# Sheet1.net
KiCad netlist of a schematic drawn in Altium Designer
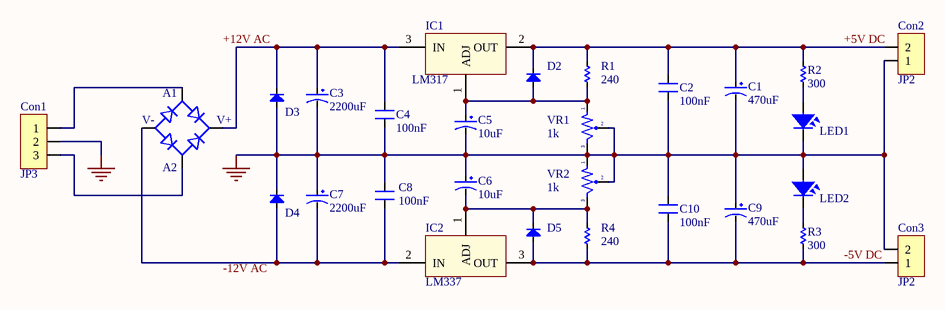
[diagram p0: Sheet1.SchDoc]

(export (version "E")
  (design (tool "Eeschema 10.0.6"))
  (components
    (comp (ref "C1")
      (value "470uF")
      (footprint "CA-ALU-6.3")
      (description "Polarized")
      (libsource (lib "KhiemLab") (part "Capacitor P"))
    )
    (comp (ref "C2")
      (value "100nF")
      (footprint "CN1.5")
      (description "Non-polarized")
      (libsource (lib "KhiemLab") (part "Capacitor NP"))
    )
    (comp (ref "C3")
      (value "2200uF")
      (footprint "CA-ALU-10")
      (description "Polarized")
      (libsource (lib "KhiemLab") (part "Capacitor P"))
    )
    (comp (ref "C4")
      (value "100nF")
      (footprint "CN1.5")
      (description "Non-polarized")
      (libsource (lib "KhiemLab") (part "Capacitor NP"))
    )
    (comp (ref "C5")
      (value "10uF")
      (footprint "CA-ALU-5")
      (description "Polarized")
      (libsource (lib "KhiemLab") (part "Capacitor P"))
    )
    (comp (ref "C6")
      (value "10uF")
      (footprint "CA-ALU-5")
      (description "Polarized")
      (libsource (lib "KhiemLab") (part "Capacitor P"))
    )
    (comp (ref "C7")
      (value "2200uF")
      (footprint "CA-ALU-10")
      (description "Polarized")
      (libsource (lib "KhiemLab") (part "Capacitor P"))
    )
    (comp (ref "C8")
      (value "100nF")
      (footprint "CN1.5")
      (description "Non-polarized")
      (libsource (lib "KhiemLab") (part "Capacitor NP"))
    )
    (comp (ref "C9")
      (value "470uF")
      (footprint "CA-ALU-6.3")
      (description "Polarized")
      (libsource (lib "KhiemLab") (part "Capacitor P"))
    )
    (comp (ref "C10")
      (value "100nF")
      (footprint "CN1.5")
      (description "Non-polarized")
      (libsource (lib "KhiemLab") (part "Capacitor NP"))
    )
    (comp (ref "Con1")
      (value "JP3")
      (footprint "KF3-3.5")
      (description "male/female")
      (fields
        (field (name "MANUFACTURER") "Würth Elektronik eiSos GmbH")
        (field (name "PARTNO") "613003143121")
        (field (name "CREATED BY") "Karrer Zheng")
      )
      (libsource (lib "KhiemLab") (part "Header 3"))
    )
    (comp (ref "Con2")
      (value "JP2")
      (footprint "KF2-3.5")
      (description "male/female")
      (fields
        (field (name "MANUFACTURER") "Würth Elektronik eiSos GmbH")
        (field (name "PARTNO") "613002143121")
        (field (name "CREATED BY") "Karrer Zheng")
      )
      (libsource (lib "KhiemLab") (part "Header 2"))
    )
    (comp (ref "Con3")
      (value "JP2")
      (footprint "KF2-3.5")
      (description "male/female")
      (fields
        (field (name "MANUFACTURER") "Würth Elektronik eiSos GmbH")
        (field (name "PARTNO") "613002143121")
        (field (name "CREATED BY") "Karrer Zheng")
      )
      (libsource (lib "KhiemLab") (part "Header 2"))
    )
    (comp (ref "D2")
      (value "Diode")
      (footprint "DIO-1A-SMALL")
      (description "Default Diode")
      (fields (field (name "PUBLISHER") "Altium Limited"))
      (libsource (lib "KhiemLab") (part "Diode"))
    )
    (comp (ref "D3")
      (value "Diode")
      (footprint "DIO-1A-SMALL")
      (description "Default Diode")
      (fields (field (name "PUBLISHER") "Altium Limited"))
      (libsource (lib "KhiemLab") (part "Diode"))
    )
    (comp (ref "D4")
      (value "Diode")
      (footprint "DIO-1A-SMALL")
      (description "Default Diode")
      (fields (field (name "PUBLISHER") "Altium Limited"))
      (libsource (lib "KhiemLab") (part "Diode"))
    )
    (comp (ref "D5")
      (value "Diode")
      (footprint "DIO-1A-SMALL")
      (description "Default Diode")
      (fields (field (name "PUBLISHER") "Altium Limited"))
      (libsource (lib "KhiemLab") (part "Diode"))
    )
    (comp (ref "DB1")
      (value "Diode Brideg")
      (footprint "DIO-Bri 5A")
      (description "Convert AC to DC voltage, 4 pin")
      (libsource (lib "KhiemLab") (part "Diode Brigde"))
    )
    (comp (ref "IC1")
      (value "LM317")
      (footprint "TO220H2")
      (description "Adj Voltage +1.2 -> +37V")
      (libsource (lib "KhiemLab") (part "LM317"))
    )
    (comp (ref "IC2")
      (value "LM337")
      (footprint "TO220H2")
      (description "On ap (-)     -1.2 -> - 37V")
      (libsource (lib "KhiemLab") (part "LM337"))
    )
    (comp (ref "LED1")
      (value "LED")
      (footprint "LED-5-RED")
      (description "LED Single colour")
      (libsource (lib "KhiemLab") (part "LED"))
    )
    (comp (ref "LED2")
      (value "LED")
      (footprint "LED-5-RED")
      (description "LED Single colour")
      (libsource (lib "KhiemLab") (part "LED"))
    )
    (comp (ref "R1")
      (value "240")
      (footprint "RES-1/4W-SMALL")
      (fields
        (field (name "MANUFACTURER") "Generic Components")
        (field (name "PUBLISHER") "Altium Hobart Technology Centre")
      )
      (libsource (lib "KhiemLab") (part "Resistor"))
    )
    (comp (ref "R2")
      (value "300")
      (footprint "RES-1/4W-SMALL")
      (fields
        (field (name "MANUFACTURER") "Generic Components")
        (field (name "PUBLISHER") "Altium Hobart Technology Centre")
      )
      (libsource (lib "KhiemLab") (part "Resistor"))
    )
    (comp (ref "R3")
      (value "300")
      (footprint "RES-1/4W-SMALL")
      (fields
        (field (name "MANUFACTURER") "Generic Components")
        (field (name "PUBLISHER") "Altium Hobart Technology Centre")
      )
      (libsource (lib "KhiemLab") (part "Resistor"))
    )
    (comp (ref "R4")
      (value "240")
      (footprint "RES-1/4W-SMALL")
      (fields
        (field (name "MANUFACTURER") "Generic Components")
        (field (name "PUBLISHER") "Altium Hobart Technology Centre")
      )
      (libsource (lib "KhiemLab") (part "Resistor"))
    )
    (comp (ref "VR1")
      (value "1k")
      (footprint "VR-S3")
      (description "Var Res")
      (libsource (lib "KhiemLab") (part "Variable Resistor"))
    )
    (comp (ref "VR2")
      (value "1k")
      (footprint "VR-S3")
      (description "Var Res")
      (libsource (lib "KhiemLab") (part "Variable Resistor"))
    )
  )
  (nets
    (net (code "1") (name "/+5V DC") (class "Default")
      (node (ref "C1") (pin "1") (pinfunction "1_1") (pintype "passive"))
      (node (ref "C2") (pin "1") (pinfunction "1_1") (pintype "passive"))
      (node (ref "Con2") (pin "2") (pinfunction "2_2") (pintype "passive"))
      (node (ref "D2") (pin "2") (pinfunction "K_2") (pintype "passive"))
      (node (ref "IC1") (pin "2") (pinfunction "OUT_2") (pintype "passive"))
      (node (ref "R1") (pin "2") (pinfunction "2_2") (pintype "passive"))
      (node (ref "R2") (pin "2") (pinfunction "2_2") (pintype "passive"))
    )
    (net (code "3") (name "/-5V DC") (class "Default")
      (node (ref "C10") (pin "1") (pinfunction "1_1") (pintype "passive"))
      (node (ref "C9") (pin "2") (pinfunction "2_2") (pintype "passive"))
      (node (ref "Con3") (pin "1") (pinfunction "1_1") (pintype "passive"))
      (node (ref "D5") (pin "1") (pinfunction "A_1") (pintype "passive"))
      (node (ref "IC2") (pin "3") (pinfunction "OUT_3") (pintype "passive"))
      (node (ref "R3") (pin "1") (pinfunction "1_1") (pintype "passive"))
      (node (ref "R4") (pin "1") (pinfunction "1_1") (pintype "passive"))
    )
    (net (code "5") (name "GND") (class "Default")
      (node (ref "C1") (pin "2") (pinfunction "2_2") (pintype "passive"))
      (node (ref "C10") (pin "2") (pinfunction "2_2") (pintype "passive"))
      (node (ref "C2") (pin "2") (pinfunction "2_2") (pintype "passive"))
      (node (ref "C3") (pin "2") (pinfunction "2_2") (pintype "passive"))
      (node (ref "C4") (pin "1") (pinfunction "1_1") (pintype "passive"))
      (node (ref "C5") (pin "2") (pinfunction "2_2") (pintype "passive"))
      (node (ref "C6") (pin "1") (pinfunction "1_1") (pintype "passive"))
      (node (ref "C7") (pin "1") (pinfunction "1_1") (pintype "passive"))
      (node (ref "C8") (pin "1") (pinfunction "1_1") (pintype "passive"))
      (node (ref "C9") (pin "1") (pinfunction "1_1") (pintype "passive"))
      (node (ref "Con1") (pin "2") (pinfunction "2_2") (pintype "passive"))
      (node (ref "Con2") (pin "1") (pinfunction "1_1") (pintype "passive"))
      (node (ref "Con3") (pin "2") (pinfunction "2_2") (pintype "passive"))
      (node (ref "D3") (pin "1") (pinfunction "A_1") (pintype "passive"))
      (node (ref "D4") (pin "2") (pinfunction "K_2") (pintype "passive"))
      (node (ref "LED1") (pin "2") (pinfunction "2_2") (pintype "passive"))
      (node (ref "LED2") (pin "1") (pinfunction "1_1") (pintype "passive"))
      (node (ref "VR1") (pin "2") (pinfunction "2_2") (pintype "passive"))
      (node (ref "VR1") (pin "3") (pinfunction "3_3") (pintype "passive"))
      (node (ref "VR2") (pin "1") (pinfunction "1_1") (pintype "passive"))
      (node (ref "VR2") (pin "2") (pinfunction "2_2") (pintype "passive"))
    )
    (net (code "6") (name "Net-(D2-A)") (class "Default")
      (node (ref "C5") (pin "1") (pinfunction "1_1") (pintype "passive"))
      (node (ref "D2") (pin "1") (pinfunction "A_1") (pintype "passive"))
      (node (ref "IC1") (pin "1") (pinfunction "ADJ_1") (pintype "passive"))
      (node (ref "R1") (pin "1") (pinfunction "1_1") (pintype "passive"))
      (node (ref "VR1") (pin "1") (pinfunction "1_1") (pintype "passive"))
    )
    (net (code "7") (name "Net-(D3-K)") (class "Default")
      (node (ref "C3") (pin "1") (pinfunction "1_1") (pintype "passive"))
      (node (ref "C4") (pin "2") (pinfunction "2_2") (pintype "passive"))
      (node (ref "D3") (pin "2") (pinfunction "K_2") (pintype "passive"))
      (node (ref "DB1") (pin "1") (pinfunction "+V_OUT_1") (pintype "passive"))
      (node (ref "IC1") (pin "3") (pinfunction "IN_3") (pintype "passive"))
    )
    (net (code "8") (name "Net-(D4-A)") (class "Default")
      (node (ref "C7") (pin "2") (pinfunction "2_2") (pintype "passive"))
      (node (ref "C8") (pin "2") (pinfunction "2_2") (pintype "passive"))
      (node (ref "D4") (pin "1") (pinfunction "A_1") (pintype "passive"))
      (node (ref "DB1") (pin "4") (pinfunction "-V_OUT_4") (pintype "passive"))
      (node (ref "IC2") (pin "2") (pinfunction "IN_2") (pintype "passive"))
    )
    (net (code "9") (name "Net-(D5-K)") (class "Default")
      (node (ref "C6") (pin "2") (pinfunction "2_2") (pintype "passive"))
      (node (ref "D5") (pin "2") (pinfunction "K_2") (pintype "passive"))
      (node (ref "IC2") (pin "1") (pinfunction "ADJ_1") (pintype "passive"))
      (node (ref "R4") (pin "2") (pinfunction "2_2") (pintype "passive"))
      (node (ref "VR2") (pin "3") (pinfunction "3_3") (pintype "passive"))
    )
    (net (code "10") (name "Net-(DB1-AC1)") (class "Default")
      (node (ref "Con1") (pin "1") (pinfunction "1_1") (pintype "passive"))
      (node (ref "DB1") (pin "2") (pinfunction "AC1_2") (pintype "passive"))
    )
    (net (code "11") (name "Net-(DB1-AC2)") (class "Default")
      (node (ref "Con1") (pin "3") (pinfunction "3_3") (pintype "passive"))
      (node (ref "DB1") (pin "3") (pinfunction "AC2_3") (pintype "passive"))
    )
    (net (code "12") (name "Net-(LED1-Pad1)") (class "Default")
      (node (ref "LED1") (pin "1") (pinfunction "1_1") (pintype "passive"))
      (node (ref "R2") (pin "1") (pinfunction "1_1") (pintype "passive"))
    )
    (net (code "13") (name "Net-(LED2-Pad2)") (class "Default")
      (node (ref "LED2") (pin "2") (pinfunction "2_2") (pintype "passive"))
      (node (ref "R3") (pin "2") (pinfunction "2_2") (pintype "passive"))
    )
  )
)
